# Keychain_Tape.net
KiCad netlist of a schematic drawn in EAGLE
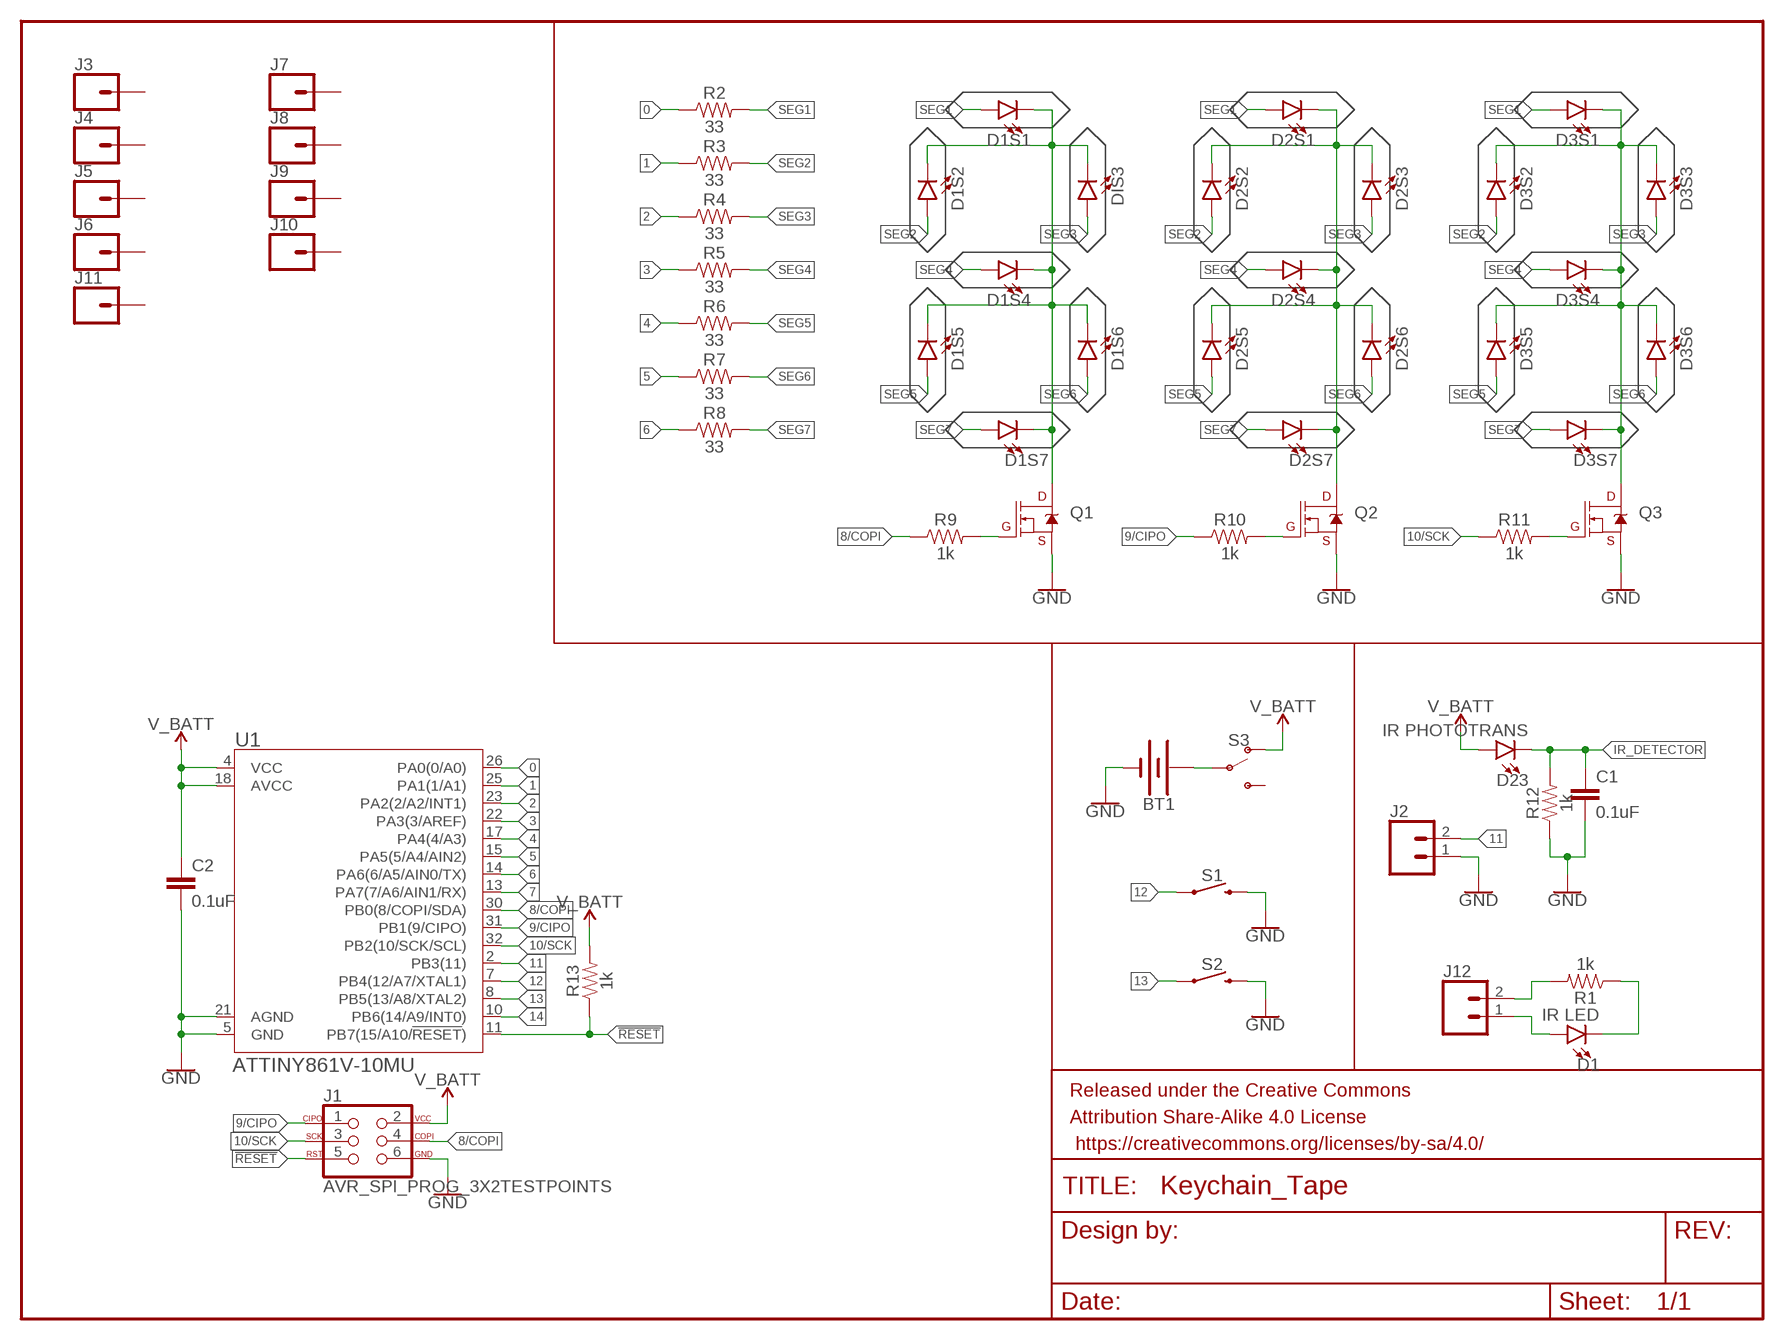
[diagram p0: schematic, sheet 1]

(export (version "E")
  (design (tool "Eeschema 10.0.6"))
  (components
    (comp (ref "BT1")
      (value "BATTERY-20MM_SMD_4LEGS_OVERPASTE_INNER")
      (footprint "eagle-import:BATTCON_20MM_4LEGS_OVERPASTE_INNER")
      (libsource (lib "eagle-import") (part "BATTERY-20MM_SMD_4LEGS_OVERPASTE_INNER"))
    )
    (comp (ref "C1")
      (value "0.1uF")
      (footprint "eagle-import:0603")
      (libsource (lib "eagle-import") (part "0.1UF-0603-25V-(+80/-20%)"))
    )
    (comp (ref "C2")
      (value "0.1uF")
      (footprint "eagle-import:0603")
      (libsource (lib "eagle-import") (part "0.1UF-0603-25V-(+80/-20%)"))
    )
    (comp (ref "D1")
      (value "IR LED")
      (footprint "eagle-import:LED-0603")
      (libsource (lib "eagle-import") (part "LED-IR0603"))
    )
    (comp (ref "D1S1")
      (value "LED0603")
      (footprint "eagle-import:LED-0603")
      (libsource (lib "eagle-import") (part "LED0603"))
    )
    (comp (ref "D1S2")
      (value "LED0603")
      (footprint "eagle-import:LED-0603")
      (libsource (lib "eagle-import") (part "LED0603"))
    )
    (comp (ref "D1S4")
      (value "LED0603")
      (footprint "eagle-import:LED-0603")
      (libsource (lib "eagle-import") (part "LED0603"))
    )
    (comp (ref "D1S5")
      (value "LED0603")
      (footprint "eagle-import:LED-0603")
      (libsource (lib "eagle-import") (part "LED0603"))
    )
    (comp (ref "D1S6")
      (value "LED0603")
      (footprint "eagle-import:LED-0603")
      (libsource (lib "eagle-import") (part "LED0603"))
    )
    (comp (ref "D1S7")
      (value "LED0603")
      (footprint "eagle-import:LED-0603")
      (libsource (lib "eagle-import") (part "LED0603"))
    )
    (comp (ref "D2S1")
      (value "LED0603")
      (footprint "eagle-import:LED-0603")
      (libsource (lib "eagle-import") (part "LED0603"))
    )
    (comp (ref "D2S2")
      (value "LED0603")
      (footprint "eagle-import:LED-0603")
      (libsource (lib "eagle-import") (part "LED0603"))
    )
    (comp (ref "D2S3")
      (value "LED0603")
      (footprint "eagle-import:LED-0603")
      (libsource (lib "eagle-import") (part "LED0603"))
    )
    (comp (ref "D2S4")
      (value "LED0603")
      (footprint "eagle-import:LED-0603")
      (libsource (lib "eagle-import") (part "LED0603"))
    )
    (comp (ref "D2S5")
      (value "LED0603")
      (footprint "eagle-import:LED-0603")
      (libsource (lib "eagle-import") (part "LED0603"))
    )
    (comp (ref "D2S6")
      (value "LED0603")
      (footprint "eagle-import:LED-0603")
      (libsource (lib "eagle-import") (part "LED0603"))
    )
    (comp (ref "D2S7")
      (value "LED0603")
      (footprint "eagle-import:LED-0603")
      (libsource (lib "eagle-import") (part "LED0603"))
    )
    (comp (ref "D3S1")
      (value "LED0603")
      (footprint "eagle-import:LED-0603")
      (libsource (lib "eagle-import") (part "LED0603"))
    )
    (comp (ref "D3S2")
      (value "LED0603")
      (footprint "eagle-import:LED-0603")
      (libsource (lib "eagle-import") (part "LED0603"))
    )
    (comp (ref "D3S3")
      (value "LED0603")
      (footprint "eagle-import:LED-0603")
      (libsource (lib "eagle-import") (part "LED0603"))
    )
    (comp (ref "D3S4")
      (value "LED0603")
      (footprint "eagle-import:LED-0603")
      (libsource (lib "eagle-import") (part "LED0603"))
    )
    (comp (ref "D3S5")
      (value "LED0603")
      (footprint "eagle-import:LED-0603")
      (libsource (lib "eagle-import") (part "LED0603"))
    )
    (comp (ref "D3S6")
      (value "LED0603")
      (footprint "eagle-import:LED-0603")
      (libsource (lib "eagle-import") (part "LED0603"))
    )
    (comp (ref "D3S7")
      (value "LED0603")
      (footprint "eagle-import:LED-0603")
      (libsource (lib "eagle-import") (part "LED0603"))
    )
    (comp (ref "D23")
      (value "IR PHOTOTRANS")
      (footprint "eagle-import:LED-0603")
      (libsource (lib "eagle-import") (part "LED-IR0603"))
    )
    (comp (ref "DIS3")
      (value "LED0603")
      (footprint "eagle-import:LED-0603")
      (libsource (lib "eagle-import") (part "LED0603"))
    )
    (comp (ref "FRAME1")
      (value "FRAME-LETTER")
      (footprint "eagle-import:CREATIVE_COMMONS")
      (libsource (lib "eagle-import") (part "FRAME-LETTER"))
    )
    (comp (ref "J1")
      (value "AVR_SPI_PROG_3X2TESTPOINTS")
      (footprint "eagle-import:2X3_TEST_POINTS")
      (libsource (lib "eagle-import") (part "AVR_SPI_PROG_3X2TESTPOINTS"))
    )
    (comp (ref "J2")
      (value "CONN_02")
      (footprint "eagle-import:1X02")
      (libsource (lib "eagle-import") (part "CONN_02"))
    )
    (comp (ref "J3")
      (value "CONN_01")
      (footprint "eagle-import:1X01")
      (libsource (lib "eagle-import") (part "CONN_01"))
    )
    (comp (ref "J4")
      (value "CONN_01")
      (footprint "eagle-import:1X01")
      (libsource (lib "eagle-import") (part "CONN_01"))
    )
    (comp (ref "J5")
      (value "CONN_01")
      (footprint "eagle-import:1X01")
      (libsource (lib "eagle-import") (part "CONN_01"))
    )
    (comp (ref "J6")
      (value "CONN_01")
      (footprint "eagle-import:1X01")
      (libsource (lib "eagle-import") (part "CONN_01"))
    )
    (comp (ref "J7")
      (value "CONN_01")
      (footprint "eagle-import:1X01")
      (libsource (lib "eagle-import") (part "CONN_01"))
    )
    (comp (ref "J8")
      (value "CONN_01")
      (footprint "eagle-import:1X01")
      (libsource (lib "eagle-import") (part "CONN_01"))
    )
    (comp (ref "J9")
      (value "CONN_01")
      (footprint "eagle-import:1X01")
      (libsource (lib "eagle-import") (part "CONN_01"))
    )
    (comp (ref "J10")
      (value "CONN_01")
      (footprint "eagle-import:1X01")
      (libsource (lib "eagle-import") (part "CONN_01"))
    )
    (comp (ref "J11")
      (value "CONN_01")
      (footprint "eagle-import:1X01")
      (libsource (lib "eagle-import") (part "CONN_01"))
    )
    (comp (ref "J12")
      (value "CONN_02")
      (footprint "eagle-import:1X02")
      (libsource (lib "eagle-import") (part "CONN_02"))
    )
    (comp (ref "Q1")
      (value "220mA/50V/3.5Ω")
      (footprint "eagle-import:SOT23-3")
      (libsource (lib "eagle-import") (part "MOSFET-NCH-BSS138"))
    )
    (comp (ref "Q2")
      (value "220mA/50V/3.5Ω")
      (footprint "eagle-import:SOT23-3")
      (libsource (lib "eagle-import") (part "MOSFET-NCH-BSS138"))
    )
    (comp (ref "Q3")
      (value "220mA/50V/3.5Ω")
      (footprint "eagle-import:SOT23-3")
      (libsource (lib "eagle-import") (part "MOSFET-NCH-BSS138"))
    )
    (comp (ref "R1")
      (value "1k")
      (footprint "eagle-import:0603")
      (libsource (lib "eagle-import") (part "1KOHM-0603-1/10W-1%"))
    )
    (comp (ref "R2")
      (value "33")
      (footprint "eagle-import:0603")
      (libsource (lib "eagle-import") (part "33OHM-0603-1/10W-1%"))
    )
    (comp (ref "R3")
      (value "33")
      (footprint "eagle-import:0603")
      (libsource (lib "eagle-import") (part "33OHM-0603-1/10W-1%"))
    )
    (comp (ref "R4")
      (value "33")
      (footprint "eagle-import:0603")
      (libsource (lib "eagle-import") (part "33OHM-0603-1/10W-1%"))
    )
    (comp (ref "R5")
      (value "33")
      (footprint "eagle-import:0603")
      (libsource (lib "eagle-import") (part "33OHM-0603-1/10W-1%"))
    )
    (comp (ref "R6")
      (value "33")
      (footprint "eagle-import:0603")
      (libsource (lib "eagle-import") (part "33OHM-0603-1/10W-1%"))
    )
    (comp (ref "R7")
      (value "33")
      (footprint "eagle-import:0603")
      (libsource (lib "eagle-import") (part "33OHM-0603-1/10W-1%"))
    )
    (comp (ref "R8")
      (value "33")
      (footprint "eagle-import:0603")
      (libsource (lib "eagle-import") (part "33OHM-0603-1/10W-1%"))
    )
    (comp (ref "R9")
      (value "1k")
      (footprint "eagle-import:0603")
      (libsource (lib "eagle-import") (part "1KOHM-0603-1/10W-1%"))
    )
    (comp (ref "R10")
      (value "1k")
      (footprint "eagle-import:0603")
      (libsource (lib "eagle-import") (part "1KOHM-0603-1/10W-1%"))
    )
    (comp (ref "R11")
      (value "1k")
      (footprint "eagle-import:0603")
      (libsource (lib "eagle-import") (part "1KOHM-0603-1/10W-1%"))
    )
    (comp (ref "R12")
      (value "1k")
      (footprint "eagle-import:0603")
      (libsource (lib "eagle-import") (part "1KOHM-0603-1/10W-1%"))
    )
    (comp (ref "R13")
      (value "1k")
      (footprint "eagle-import:0603")
      (libsource (lib "eagle-import") (part "1KOHM-0603-1/10W-1%"))
    )
    (comp (ref "S1")
      (value "MOMENTARY-SWITCH-SPST-SMD-5.2MM-TALL")
      (footprint "eagle-import:TACTILE_SWITCH_SMD_5.2MM")
      (libsource (lib "eagle-import") (part "MOMENTARY-SWITCH-SPST-SMD-5.2MM-TALL"))
    )
    (comp (ref "S2")
      (value "MOMENTARY-SWITCH-SPST-SMD-5.2MM-TALL")
      (footprint "eagle-import:TACTILE_SWITCH_SMD_5.2MM")
      (libsource (lib "eagle-import") (part "MOMENTARY-SWITCH-SPST-SMD-5.2MM-TALL"))
    )
    (comp (ref "S3")
      (value "SWITCH-SPDT-SMD-RIGHT-ANGLE")
      (footprint "eagle-import:SWITCH_SPST_SMD_A")
      (libsource (lib "eagle-import") (part "SWITCH-SPDT-SMD-RIGHT-ANGLE"))
    )
    (comp (ref "U1")
      (value "ATTINY861V-10MU")
      (footprint "eagle-import:32M1-A_ATM")
      (fields (field (name "COPYRIGHT") "Copyright (C) 2021 Ultra Librarian. All rights reserved."))
      (libsource (lib "eagle-import") (part "ATTINY861V-10MU"))
    )
  )
  (nets
    (net (code "1") (name "/~{RESET}") (class "Default")
      (node (ref "J1") (pin "5") (pinfunction "5_5") (pintype "passive"))
      (node (ref "R13") (pin "1") (pinfunction "1_1") (pintype "passive"))
      (node (ref "U1") (pin "11") (pinfunction "PB7(15/A10/~{RESET})_11") (pintype "bidirectional"))
    )
    (net (code "2") (name "0") (class "Default")
      (node (ref "R2") (pin "1") (pinfunction "1_1") (pintype "passive"))
      (node (ref "U1") (pin "26") (pinfunction "PA0(0/A0)_26") (pintype "bidirectional"))
    )
    (net (code "3") (name "1") (class "Default")
      (node (ref "R3") (pin "1") (pinfunction "1_1") (pintype "passive"))
      (node (ref "U1") (pin "25") (pinfunction "PA1(1/A1)_25") (pintype "bidirectional"))
    )
    (net (code "4") (name "2") (class "Default")
      (node (ref "R4") (pin "1") (pinfunction "1_1") (pintype "passive"))
      (node (ref "U1") (pin "23") (pinfunction "PA2(2/A2/INT1)_23") (pintype "bidirectional"))
    )
    (net (code "5") (name "3") (class "Default")
      (node (ref "R5") (pin "1") (pinfunction "1_1") (pintype "passive"))
      (node (ref "U1") (pin "22") (pinfunction "PA3(3/AREF)_22") (pintype "bidirectional"))
    )
    (net (code "6") (name "4") (class "Default")
      (node (ref "R6") (pin "1") (pinfunction "1_1") (pintype "passive"))
      (node (ref "U1") (pin "17") (pinfunction "PA4(4/A3)_17") (pintype "bidirectional"))
    )
    (net (code "7") (name "5") (class "Default")
      (node (ref "R7") (pin "1") (pinfunction "1_1") (pintype "passive"))
      (node (ref "U1") (pin "15") (pinfunction "PA5(5/A4/AIN2)_15") (pintype "bidirectional"))
    )
    (net (code "8") (name "6") (class "Default")
      (node (ref "R8") (pin "1") (pinfunction "1_1") (pintype "passive"))
      (node (ref "U1") (pin "14") (pinfunction "PA6(6/A5/AIN0/TX)_14") (pintype "bidirectional"))
    )
    (net (code "9") (name "7") (class "Default")
      (node (ref "U1") (pin "13") (pinfunction "PA7(7/A6/AIN1/RX)_13") (pintype "bidirectional"))
    )
    (net (code "10") (name "8{slash}COPI") (class "Default")
      (node (ref "J1") (pin "4") (pinfunction "4_4") (pintype "passive"))
      (node (ref "R9") (pin "1") (pinfunction "1_1") (pintype "passive"))
      (node (ref "U1") (pin "30") (pinfunction "PB0(8/COPI/SDA)_30") (pintype "bidirectional"))
    )
    (net (code "11") (name "9{slash}CIPO") (class "Default")
      (node (ref "J1") (pin "1") (pinfunction "1_1") (pintype "passive"))
      (node (ref "R10") (pin "1") (pinfunction "1_1") (pintype "passive"))
      (node (ref "U1") (pin "31") (pinfunction "PB1(9/CIPO)_31") (pintype "bidirectional"))
    )
    (net (code "12") (name "10{slash}SCK") (class "Default")
      (node (ref "J1") (pin "3") (pinfunction "3_3") (pintype "passive"))
      (node (ref "R11") (pin "1") (pinfunction "1_1") (pintype "passive"))
      (node (ref "U1") (pin "32") (pinfunction "PB2(10/SCK/SCL)_32") (pintype "bidirectional"))
    )
    (net (code "13") (name "11") (class "Default")
      (node (ref "J2") (pin "2") (pinfunction "2_2") (pintype "passive"))
      (node (ref "U1") (pin "2") (pinfunction "PB3(11)_2") (pintype "bidirectional"))
    )
    (net (code "14") (name "12") (class "Default")
      (node (ref "S1") (pin "1") (pinfunction "1_1") (pintype "passive"))
      (node (ref "U1") (pin "7") (pinfunction "PB4(12/A7/XTAL1)_7") (pintype "bidirectional"))
    )
    (net (code "15") (name "13") (class "Default")
      (node (ref "S2") (pin "1") (pinfunction "1_1") (pintype "passive"))
      (node (ref "U1") (pin "8") (pinfunction "PB5(13/A8/XTAL2)_8") (pintype "bidirectional"))
    )
    (net (code "16") (name "14") (class "Default")
      (node (ref "U1") (pin "10") (pinfunction "PB6(14/A9/INT0)_10") (pintype "bidirectional"))
    )
    (net (code "17") (name "GND") (class "Default")
      (node (ref "BT1") (pin "2") (pinfunction "-_2") (pintype "power_in"))
      (node (ref "C1") (pin "2") (pinfunction "2_2") (pintype "passive"))
      (node (ref "C2") (pin "2") (pinfunction "2_2") (pintype "passive"))
      (node (ref "J1") (pin "6") (pinfunction "6_6") (pintype "passive"))
      (node (ref "J2") (pin "1") (pinfunction "1_1") (pintype "passive"))
      (node (ref "Q1") (pin "2") (pinfunction "S_2") (pintype "bidirectional"))
      (node (ref "Q2") (pin "2") (pinfunction "S_2") (pintype "bidirectional"))
      (node (ref "Q3") (pin "2") (pinfunction "S_2") (pintype "bidirectional"))
      (node (ref "R12") (pin "1") (pinfunction "1_1") (pintype "passive"))
      (node (ref "S1") (pin "3") (pinfunction "2_3") (pintype "passive"))
      (node (ref "S2") (pin "3") (pinfunction "2_3") (pintype "passive"))
      (node (ref "U1") (pin "21") (pinfunction "AGND_21") (pintype "power_in"))
      (node (ref "U1") (pin "5") (pinfunction "GND_5") (pintype "power_in"))
    )
    (net (code "18") (name "IR_DETECTOR") (class "Default")
      (node (ref "C1") (pin "1") (pinfunction "1_1") (pintype "passive"))
      (node (ref "D23") (pin "C") (pinfunction "C_C") (pintype "passive"))
      (node (ref "R12") (pin "2") (pinfunction "2_2") (pintype "passive"))
    )
    (net (code "19") (name "Net-(BT1-+)") (class "Default")
      (node (ref "BT1") (pin "1") (pinfunction "+_1") (pintype "power_in"))
      (node (ref "S3") (pin "2") (pinfunction "P_2") (pintype "passive"))
    )
    (net (code "20") (name "Net-(D1-PadA)") (class "Default")
      (node (ref "D1") (pin "A") (pinfunction "A_A") (pintype "passive"))
      (node (ref "J12") (pin "1") (pinfunction "1_1") (pintype "passive"))
    )
    (net (code "21") (name "Net-(D1-PadC)") (class "Default")
      (node (ref "D1") (pin "C") (pinfunction "C_C") (pintype "passive"))
      (node (ref "R1") (pin "1") (pinfunction "1_1") (pintype "passive"))
    )
    (net (code "22") (name "Net-(J12-Pad2)") (class "Default")
      (node (ref "J12") (pin "2") (pinfunction "2_2") (pintype "passive"))
      (node (ref "R1") (pin "2") (pinfunction "2_2") (pintype "passive"))
    )
    (net (code "23") (name "Net-(Q1-D)") (class "Default")
      (node (ref "D1S1") (pin "C") (pinfunction "C_C") (pintype "passive"))
      (node (ref "D1S2") (pin "C") (pinfunction "C_C") (pintype "passive"))
      (node (ref "D1S4") (pin "C") (pinfunction "C_C") (pintype "passive"))
      (node (ref "D1S5") (pin "C") (pinfunction "C_C") (pintype "passive"))
      (node (ref "D1S6") (pin "C") (pinfunction "C_C") (pintype "passive"))
      (node (ref "D1S7") (pin "C") (pinfunction "C_C") (pintype "passive"))
      (node (ref "DIS3") (pin "C") (pinfunction "C_C") (pintype "passive"))
      (node (ref "Q1") (pin "3") (pinfunction "D_3") (pintype "bidirectional"))
    )
    (net (code "24") (name "Net-(Q1-G)") (class "Default")
      (node (ref "Q1") (pin "1") (pinfunction "G_1") (pintype "bidirectional"))
      (node (ref "R9") (pin "2") (pinfunction "2_2") (pintype "passive"))
    )
    (net (code "25") (name "Net-(Q2-D)") (class "Default")
      (node (ref "D2S1") (pin "C") (pinfunction "C_C") (pintype "passive"))
      (node (ref "D2S2") (pin "C") (pinfunction "C_C") (pintype "passive"))
      (node (ref "D2S3") (pin "C") (pinfunction "C_C") (pintype "passive"))
      (node (ref "D2S4") (pin "C") (pinfunction "C_C") (pintype "passive"))
      (node (ref "D2S5") (pin "C") (pinfunction "C_C") (pintype "passive"))
      (node (ref "D2S6") (pin "C") (pinfunction "C_C") (pintype "passive"))
      (node (ref "D2S7") (pin "C") (pinfunction "C_C") (pintype "passive"))
      (node (ref "Q2") (pin "3") (pinfunction "D_3") (pintype "bidirectional"))
    )
    (net (code "26") (name "Net-(Q2-G)") (class "Default")
      (node (ref "Q2") (pin "1") (pinfunction "G_1") (pintype "bidirectional"))
      (node (ref "R10") (pin "2") (pinfunction "2_2") (pintype "passive"))
    )
    (net (code "27") (name "Net-(Q3-D)") (class "Default")
      (node (ref "D3S1") (pin "C") (pinfunction "C_C") (pintype "passive"))
      (node (ref "D3S2") (pin "C") (pinfunction "C_C") (pintype "passive"))
      (node (ref "D3S3") (pin "C") (pinfunction "C_C") (pintype "passive"))
      (node (ref "D3S4") (pin "C") (pinfunction "C_C") (pintype "passive"))
      (node (ref "D3S5") (pin "C") (pinfunction "C_C") (pintype "passive"))
      (node (ref "D3S6") (pin "C") (pinfunction "C_C") (pintype "passive"))
      (node (ref "D3S7") (pin "C") (pinfunction "C_C") (pintype "passive"))
      (node (ref "Q3") (pin "3") (pinfunction "D_3") (pintype "bidirectional"))
    )
    (net (code "28") (name "Net-(Q3-G)") (class "Default")
      (node (ref "Q3") (pin "1") (pinfunction "G_1") (pintype "bidirectional"))
      (node (ref "R11") (pin "2") (pinfunction "2_2") (pintype "passive"))
    )
    (net (code "29") (name "SEG1") (class "Default")
      (node (ref "D1S1") (pin "A") (pinfunction "A_A") (pintype "passive"))
      (node (ref "D2S1") (pin "A") (pinfunction "A_A") (pintype "passive"))
      (node (ref "D3S1") (pin "A") (pinfunction "A_A") (pintype "passive"))
      (node (ref "R2") (pin "2") (pinfunction "2_2") (pintype "passive"))
    )
    (net (code "30") (name "SEG2") (class "Default")
      (node (ref "D1S2") (pin "A") (pinfunction "A_A") (pintype "passive"))
      (node (ref "D2S2") (pin "A") (pinfunction "A_A") (pintype "passive"))
      (node (ref "D3S2") (pin "A") (pinfunction "A_A") (pintype "passive"))
      (node (ref "R3") (pin "2") (pinfunction "2_2") (pintype "passive"))
    )
    (net (code "31") (name "SEG3") (class "Default")
      (node (ref "D2S3") (pin "A") (pinfunction "A_A") (pintype "passive"))
      (node (ref "D3S3") (pin "A") (pinfunction "A_A") (pintype "passive"))
      (node (ref "DIS3") (pin "A") (pinfunction "A_A") (pintype "passive"))
      (node (ref "R4") (pin "2") (pinfunction "2_2") (pintype "passive"))
    )
    (net (code "32") (name "SEG4") (class "Default")
      (node (ref "D1S4") (pin "A") (pinfunction "A_A") (pintype "passive"))
      (node (ref "D2S4") (pin "A") (pinfunction "A_A") (pintype "passive"))
      (node (ref "D3S4") (pin "A") (pinfunction "A_A") (pintype "passive"))
      (node (ref "R5") (pin "2") (pinfunction "2_2") (pintype "passive"))
    )
    (net (code "33") (name "SEG5") (class "Default")
      (node (ref "D1S5") (pin "A") (pinfunction "A_A") (pintype "passive"))
      (node (ref "D2S5") (pin "A") (pinfunction "A_A") (pintype "passive"))
      (node (ref "D3S5") (pin "A") (pinfunction "A_A") (pintype "passive"))
      (node (ref "R6") (pin "2") (pinfunction "2_2") (pintype "passive"))
    )
    (net (code "34") (name "SEG6") (class "Default")
      (node (ref "D1S6") (pin "A") (pinfunction "A_A") (pintype "passive"))
      (node (ref "D2S6") (pin "A") (pinfunction "A_A") (pintype "passive"))
      (node (ref "D3S6") (pin "A") (pinfunction "A_A") (pintype "passive"))
      (node (ref "R7") (pin "2") (pinfunction "2_2") (pintype "passive"))
    )
    (net (code "35") (name "SEG7") (class "Default")
      (node (ref "D1S7") (pin "A") (pinfunction "A_A") (pintype "passive"))
      (node (ref "D2S7") (pin "A") (pinfunction "A_A") (pintype "passive"))
      (node (ref "D3S7") (pin "A") (pinfunction "A_A") (pintype "passive"))
      (node (ref "R8") (pin "2") (pinfunction "2_2") (pintype "passive"))
    )
    (net (code "36") (name "V_BATT") (class "Default")
      (node (ref "C2") (pin "1") (pinfunction "1_1") (pintype "passive"))
      (node (ref "D23") (pin "A") (pinfunction "A_A") (pintype "passive"))
      (node (ref "J1") (pin "2") (pinfunction "2_2") (pintype "passive"))
      (node (ref "R13") (pin "2") (pinfunction "2_2") (pintype "passive"))
      (node (ref "S3") (pin "1") (pinfunction "O_1") (pintype "passive"))
      (node (ref "U1") (pin "18") (pinfunction "AVCC_18") (pintype "power_in"))
      (node (ref "U1") (pin "4") (pinfunction "VCC_4") (pintype "power_in"))
    )
    (net (code "37") (name "unconnected-(J3-Pad1)") (class "Default")
      (node (ref "J3") (pin "1") (pinfunction "1_1") (pintype "passive"))
    )
    (net (code "38") (name "unconnected-(J4-Pad1)") (class "Default")
      (node (ref "J4") (pin "1") (pinfunction "1_1") (pintype "passive"))
    )
    (net (code "39") (name "unconnected-(J5-Pad1)") (class "Default")
      (node (ref "J5") (pin "1") (pinfunction "1_1") (pintype "passive"))
    )
    (net (code "40") (name "unconnected-(J6-Pad1)") (class "Default")
      (node (ref "J6") (pin "1") (pinfunction "1_1") (pintype "passive"))
    )
    (net (code "41") (name "unconnected-(J7-Pad1)") (class "Default")
      (node (ref "J7") (pin "1") (pinfunction "1_1") (pintype "passive"))
    )
    (net (code "42") (name "unconnected-(J8-Pad1)") (class "Default")
      (node (ref "J8") (pin "1") (pinfunction "1_1") (pintype "passive"))
    )
    (net (code "43") (name "unconnected-(J9-Pad1)") (class "Default")
      (node (ref "J9") (pin "1") (pinfunction "1_1") (pintype "passive"))
    )
    (net (code "44") (name "unconnected-(J10-Pad1)") (class "Default")
      (node (ref "J10") (pin "1") (pinfunction "1_1") (pintype "passive"))
    )
    (net (code "45") (name "unconnected-(J11-Pad1)") (class "Default")
      (node (ref "J11") (pin "1") (pinfunction "1_1") (pintype "passive"))
    )
    (net (code "46") (name "unconnected-(S3-S-Pad3)") (class "Default")
      (node (ref "S3") (pin "3") (pinfunction "S_3") (pintype "passive"))
    )
  )
)
